# PCB_Oven_Sch.net
KiCad netlist of a schematic drawn in Altium Designer
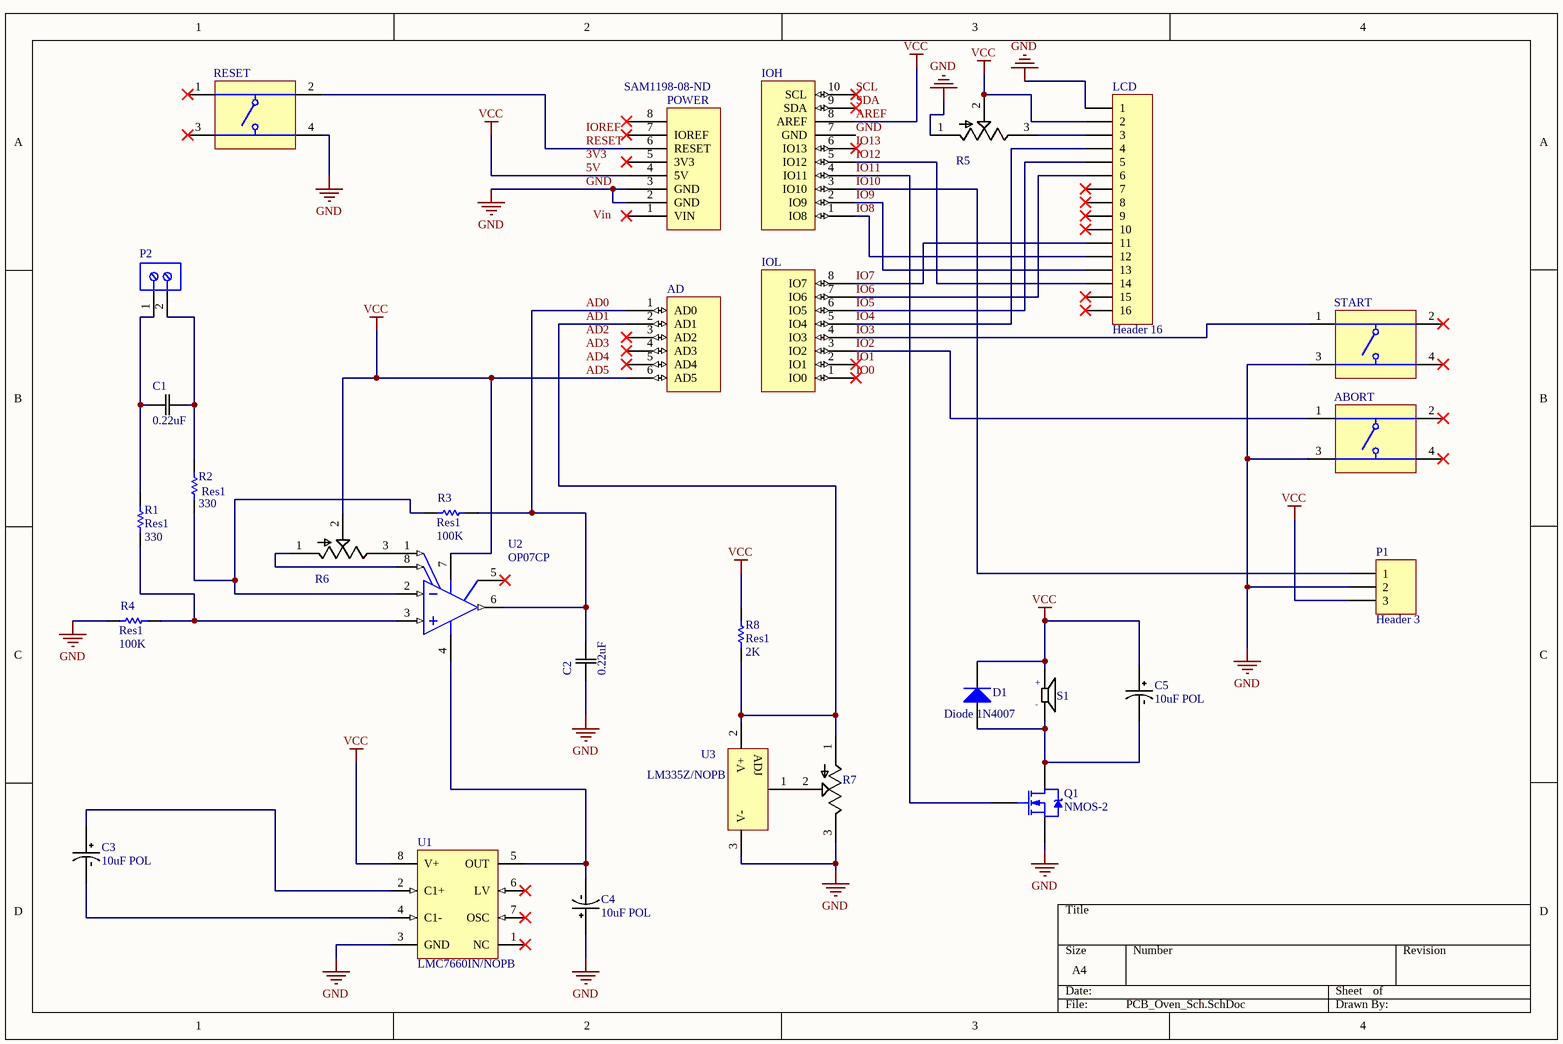
[diagram p0: PCB_Oven_Sch.SchDoc]

(export (version "E")
  (design (tool "Eeschema 10.0.6"))
  (components
    (comp (ref "ABORT")
      (value "1825910-6")
      (footprint "TECO-1825910-6_V")
      (description "Tact Switch, SPST-NO, 0.05 A, -35 to 85 degC, 4-Pin THD, RoHS, Bulk")
      (fields (field (name "MANUFACTURER") "TE Connectivity"))
      (libsource (lib "Altium Content Vault") (part "SW-SPST-4_A"))
    )
    (comp (ref "AD")
      (value "AD")
      (footprint "Header:Header 6x1 8.5mm")
      (libsource (lib "Header") (part "AD"))
    )
    (comp (ref "C1")
      (value "0.22uF")
      (footprint "0.22uF Thru hole")
      (description "CAP CER 0.22UF 200V")
      (fields (field (name "MP") "C317C221K2G5TA7301") (field (name "MF") "KEMET"))
      (libsource (lib "AltiumLibraries") (part "CAP 0.22uF"))
    )
    (comp (ref "C2")
      (value "0.22uF")
      (footprint "0.22uF Thru hole")
      (description "CAP CER 0.22UF 200V")
      (fields (field (name "MP") "C317C221K2G5TA7301") (field (name "MF") "KEMET"))
      (libsource (lib "AltiumLibraries") (part "CAP 0.22uF"))
    )
    (comp (ref "C3")
      (value "10uF POL")
      (footprint "CAP POL 10uF THRU")
      (description "CAP ALUM 10UF 20% 50V RADIAL")
      (fields (field (name "TOLERANCE") "20%") (field (name "MP") "ECA-1HM100I"))
      (libsource (lib "AltiumLibraries") (part "CAP POL 10uF THRU"))
    )
    (comp (ref "C4")
      (value "10uF POL")
      (footprint "CAP POL 10uF THRU")
      (description "CAP ALUM 10UF 20% 50V RADIAL")
      (fields (field (name "TOLERANCE") "20%") (field (name "MP") "ECA-1HM100I"))
      (libsource (lib "AltiumLibraries") (part "CAP POL 10uF THRU"))
    )
    (comp (ref "C5")
      (value "10uF POL")
      (footprint "CAP POL 10uF THRU")
      (description "CAP ALUM 10UF 20% 50V RADIAL")
      (fields (field (name "TOLERANCE") "20%") (field (name "MP") "ECA-1HM100I"))
      (libsource (lib "AltiumLibraries") (part "CAP POL 10uF THRU"))
    )
    (comp (ref "D1")
      (value "Diode 1N4007")
      (footprint "DO-41")
      (description "1 Amp General Purpose Rectifier")
      (fields (field (name "PUBLISHER") "Altium Limited"))
      (libsource (lib "Miscellaneous Devices") (part "Diode 1N4007"))
    )
    (comp (ref "IOH")
      (value "IOH")
      (footprint "Header:Header 10x1 8.5mm")
      (libsource (lib "Header") (part "IOH"))
    )
    (comp (ref "IOL") (value "IOL") (footprint "Header 8x1 8.5mm") (libsource (lib "Header") (part "IOL")))
    (comp (ref "LCD")
      (value "Header 16")
      (footprint "HDR1X16")
      (description "Header, 16-Pin")
      (fields (field (name "PUBLISHER") "Altium Limited"))
      (libsource (lib "Miscellaneous Connectors") (part "Header 16"))
    )
    (comp (ref "P1")
      (value "Header 3")
      (footprint "HDR1X3")
      (description "Header, 3-Pin")
      (fields (field (name "PUBLISHER") "Altium Limited"))
      (libsource (lib "Miscellaneous Connectors") (part "Header 3"))
    )
    (comp (ref "P2")
      (value "282836-2")
      (footprint "TECO-282836-2_V")
      (description "Female Header, Pitch 5 mm, 1 x 2 Position, Height 10 mm, Tail Length 3.5 mm, Rohs, Bulk")
      (fields (field (name "VOLTAGE") "300V") (field (name "MANUFACTURER") "TE Connectivity"))
      (libsource (lib "Altium Content Vault") (part "CN-1P-F-TB2"))
    )
    (comp (ref "POWER")
      (value "POWER_UNO")
      (footprint "Header 8x1 8.5mm")
      (fields (field (name "SUPPLIER PART NUMBER 1") "SAM1198-08-ND"))
      (libsource (lib "Header") (part "POWER_UNO"))
    )
    (comp (ref "Q1")
      (value "NMOS-2")
      (footprint "TO-220AB")
      (description "N-Channel Power MOSFET")
      (fields (field (name "PUBLISHER") "Altium Limited"))
      (libsource (lib "Miscellaneous Devices") (part "NMOS-2"))
    )
    (comp (ref "R1")
      (value "Res1")
      (footprint "AXIAL-0.3")
      (description "Resistor")
      (fields (field (name "ALTIUM_VALUE") "330") (field (name "PUBLISHER") "Altium Limited"))
      (libsource (lib "Miscellaneous Devices") (part "Res1"))
    )
    (comp (ref "R2")
      (value "Res1")
      (footprint "AXIAL-0.3")
      (description "Resistor")
      (fields (field (name "ALTIUM_VALUE") "330") (field (name "PUBLISHER") "Altium Limited"))
      (libsource (lib "Miscellaneous Devices") (part "Res1"))
    )
    (comp (ref "R3")
      (value "Res1")
      (footprint "AXIAL-0.3")
      (description "Resistor")
      (fields (field (name "ALTIUM_VALUE") "100K") (field (name "PUBLISHER") "Altium Limited"))
      (libsource (lib "Miscellaneous Devices") (part "Res1"))
    )
    (comp (ref "R4")
      (value "Res1")
      (footprint "AXIAL-0.3")
      (description "Resistor")
      (fields (field (name "ALTIUM_VALUE") "100K") (field (name "PUBLISHER") "Altium Limited"))
      (libsource (lib "Miscellaneous Devices") (part "Res1"))
    )
    (comp (ref "R5")
      (value "20K")
      (footprint "Potentiometer 20K")
      (description "TRIMMER 20K OHM 0.5W PC PIN TOP - Phillips Screw head")
      (fields (field (name "MF") "Bourns Inc.") (field (name "MP") "3362P-1-203RLF"))
      (libsource (lib "AltiumLibraries") (part "POT 20K THRU"))
    )
    (comp (ref "R6")
      (value "20K")
      (footprint "Potentiometer 20K")
      (description "TRIMMER 20K OHM 0.5W PC PIN TOP - Phillips Screw head")
      (fields (field (name "MF") "Bourns Inc.") (field (name "MP") "3362P-1-203RLF"))
      (libsource (lib "AltiumLibraries") (part "POT 20K THRU"))
    )
    (comp (ref "R7")
      (value "20K")
      (footprint "Potentiometer 20K")
      (description "TRIMMER 20K OHM 0.5W PC PIN TOP - Phillips Screw head")
      (fields (field (name "MF") "Bourns Inc.") (field (name "MP") "3362P-1-203RLF"))
      (libsource (lib "AltiumLibraries") (part "POT 20K THRU"))
    )
    (comp (ref "R8")
      (value "Res1")
      (footprint "AXIAL-0.3")
      (description "Resistor")
      (fields (field (name "ALTIUM_VALUE") "2K") (field (name "PUBLISHER") "Altium Limited"))
      (libsource (lib "Miscellaneous Devices") (part "Res1"))
    )
    (comp (ref "RESET")
      (value "1825910-6")
      (footprint "TECO-1825910-6_V")
      (description "Tact Switch, SPST-NO, 0.05 A, -35 to 85 degC, 4-Pin THD, RoHS, Bulk")
      (fields (field (name "MANUFACTURER") "TE Connectivity"))
      (libsource (lib "Altium Content Vault") (part "SW-SPST-4_A"))
    )
    (comp (ref "S1")
      (value "CEM-1203(42) THRU")
      (footprint "CEM-1203")
      (description "35mA 2.048kHz 85dB @ 3.5V")
      (fields (field (name "MP") "CEM-1203(42)") (field (name "MF") "CUI Devices"))
      (libsource (lib "AltiumLibraries") (part "CEM-1203(42) THRU"))
    )
    (comp (ref "START")
      (value "1825910-6")
      (footprint "TECO-1825910-6_V")
      (description "Tact Switch, SPST-NO, 0.05 A, -35 to 85 degC, 4-Pin THD, RoHS, Bulk")
      (fields (field (name "MANUFACTURER") "TE Connectivity"))
      (libsource (lib "Altium Content Vault") (part "SW-SPST-4_A"))
    )
    (comp (ref "U1")
      (value "LMC7660IN/NOPB")
      (footprint "P0008A")
      (description "Switched Capacitor Voltage Converter, 8-pin MDIP, Pb-Free")
      (fields (field (name "MANUFACTURER") "Texas Instruments"))
      (libsource (lib "Altium Content Vault") (part "PM-CHP-LMC7660IM-8"))
    )
    (comp (ref "U2")
      (value "OP07CP")
      (footprint "P0008A")
      (description "Low-Offset Voltage Operational Amplifier, 6 to 36 V, 0 to 70 degC, 8-pin DIP (P8), Pb-Free (RoHS)")
      (fields (field (name "MANUFACTURER") "Texas Instruments"))
      (libsource (lib "Altium Content Vault") (part "TI-OP07X-X8"))
    )
    (comp (ref "U3")
      (value "LM335Z/NOPB")
      (footprint "LP0003A")
      (description "Precision Temperature Sensor, 3-pin TO-92, Pb-Free")
      (fields (field (name "MANUFACTURER") "Texas Instruments"))
      (libsource (lib "Altium Content Vault") (part "SEN-TEMP-LM335-3"))
    )
  )
  (nets
    (net (code "3") (name "/AD0") (class "Default")
      (node (ref "AD") (pin "1") (pinfunction "AD0_1") (pintype "bidirectional"))
      (node (ref "C2") (pin "2") (pinfunction "C2_2") (pintype "passive"))
      (node (ref "R3") (pin "1") (pinfunction "1_1") (pintype "passive"))
      (node (ref "U2") (pin "6") (pinfunction "OUT_6") (pintype "output"))
    )
    (net (code "4") (name "/AD1") (class "Default")
      (node (ref "AD") (pin "2") (pinfunction "AD1_2") (pintype "bidirectional"))
      (node (ref "R7") (pin "1") (pinfunction "CCW_1") (pintype "passive"))
      (node (ref "R8") (pin "2") (pinfunction "2_2") (pintype "passive"))
      (node (ref "U3") (pin "2") (pinfunction "V+_2") (pintype "passive"))
    )
    (net (code "8") (name "/IO0") (class "Default")
      (node (ref "IOL") (pin "1") (pinfunction "IO0_1") (pintype "bidirectional+no_connect"))
    )
    (net (code "9") (name "/IO1") (class "Default")
      (node (ref "IOL") (pin "2") (pinfunction "IO1_2") (pintype "bidirectional+no_connect"))
    )
    (net (code "10") (name "/IO2") (class "Default")
      (node (ref "ABORT") (pin "1") (pinfunction "1_1") (pintype "passive"))
      (node (ref "IOL") (pin "3") (pinfunction "IO2_3") (pintype "bidirectional"))
    )
    (net (code "11") (name "/IO3") (class "Default")
      (node (ref "IOL") (pin "4") (pinfunction "IO3_4") (pintype "bidirectional"))
      (node (ref "START") (pin "1") (pinfunction "1_1") (pintype "passive"))
    )
    (net (code "12") (name "/IO4") (class "Default")
      (node (ref "IOL") (pin "5") (pinfunction "IO4_5") (pintype "bidirectional"))
      (node (ref "LCD") (pin "4") (pinfunction "4_4") (pintype "passive"))
    )
    (net (code "13") (name "/IO5") (class "Default")
      (node (ref "IOL") (pin "6") (pinfunction "IO5_6") (pintype "bidirectional"))
      (node (ref "LCD") (pin "5") (pinfunction "5_5") (pintype "passive"))
    )
    (net (code "14") (name "/IO6") (class "Default")
      (node (ref "IOL") (pin "7") (pinfunction "IO6_7") (pintype "bidirectional"))
      (node (ref "LCD") (pin "6") (pinfunction "6_6") (pintype "passive"))
    )
    (net (code "15") (name "/IO7") (class "Default")
      (node (ref "IOL") (pin "8") (pinfunction "IO7_8") (pintype "bidirectional"))
      (node (ref "LCD") (pin "11") (pinfunction "11_11") (pintype "passive"))
    )
    (net (code "16") (name "/IO8") (class "Default")
      (node (ref "IOH") (pin "1") (pinfunction "IO8_1") (pintype "bidirectional"))
      (node (ref "LCD") (pin "12") (pinfunction "12_12") (pintype "passive"))
    )
    (net (code "17") (name "/IO9") (class "Default")
      (node (ref "IOH") (pin "2") (pinfunction "IO9_2") (pintype "bidirectional"))
      (node (ref "LCD") (pin "13") (pinfunction "13_13") (pintype "passive"))
    )
    (net (code "18") (name "/IO10") (class "Default")
      (node (ref "IOH") (pin "3") (pinfunction "IO10_3") (pintype "bidirectional"))
      (node (ref "P1") (pin "1") (pinfunction "1_1") (pintype "passive"))
    )
    (net (code "19") (name "/IO11") (class "Default")
      (node (ref "IOH") (pin "4") (pinfunction "IO11_4") (pintype "bidirectional"))
      (node (ref "Q1") (pin "1") (pinfunction "G_1") (pintype "passive"))
    )
    (net (code "20") (name "/IO12") (class "Default")
      (node (ref "IOH") (pin "5") (pinfunction "IO12_5") (pintype "bidirectional"))
      (node (ref "LCD") (pin "14") (pinfunction "14_14") (pintype "passive"))
    )
    (net (code "21") (name "/IO13") (class "Default")
      (node (ref "IOH") (pin "6") (pinfunction "IO13_6") (pintype "bidirectional+no_connect"))
    )
    (net (code "23") (name "/RESET") (class "Default")
      (node (ref "POWER") (pin "6") (pinfunction "RESET_6") (pintype "passive"))
      (node (ref "RESET") (pin "2") (pinfunction "2_2") (pintype "passive"))
    )
    (net (code "24") (name "/SCL") (class "Default")
      (node (ref "IOH") (pin "10") (pinfunction "SCL_10") (pintype "bidirectional+no_connect"))
    )
    (net (code "25") (name "/SDA") (class "Default")
      (node (ref "IOH") (pin "9") (pinfunction "SDA_9") (pintype "bidirectional+no_connect"))
    )
    (net (code "27") (name "GND") (class "Default")
      (node (ref "ABORT") (pin "3") (pinfunction "3_3") (pintype "passive"))
      (node (ref "C2") (pin "1") (pinfunction "C1_1") (pintype "passive"))
      (node (ref "C4") (pin "POS") (pinfunction "POS_POS") (pintype "passive"))
      (node (ref "IOH") (pin "7") (pinfunction "GND_7") (pintype "power_in"))
      (node (ref "LCD") (pin "1") (pinfunction "1_1") (pintype "passive"))
      (node (ref "P1") (pin "2") (pinfunction "2_2") (pintype "passive"))
      (node (ref "POWER") (pin "2") (pinfunction "GND_2") (pintype "power_in"))
      (node (ref "POWER") (pin "3") (pinfunction "GND_3") (pintype "power_in"))
      (node (ref "Q1") (pin "3") (pinfunction "S_3") (pintype "passive"))
      (node (ref "R4") (pin "2") (pinfunction "2_2") (pintype "passive"))
      (node (ref "R5") (pin "1") (pinfunction "CCW_1") (pintype "passive"))
      (node (ref "R7") (pin "3") (pinfunction "CW_3") (pintype "passive"))
      (node (ref "RESET") (pin "4") (pinfunction "4_4") (pintype "passive"))
      (node (ref "START") (pin "3") (pinfunction "3_3") (pintype "passive"))
      (node (ref "U1") (pin "3") (pinfunction "GND_3") (pintype "power_in"))
      (node (ref "U3") (pin "3") (pinfunction "V-_3") (pintype "passive"))
    )
    (net (code "28") (name "Net-(C1-C1)") (class "Default")
      (node (ref "C1") (pin "1") (pinfunction "C1_1") (pintype "passive"))
      (node (ref "P2") (pin "1") (pinfunction "1_1") (pintype "passive"))
      (node (ref "R1") (pin "2") (pinfunction "2_2") (pintype "passive"))
    )
    (net (code "29") (name "Net-(C1-C2)") (class "Default")
      (node (ref "C1") (pin "2") (pinfunction "C2_2") (pintype "passive"))
      (node (ref "P2") (pin "2") (pinfunction "2_2") (pintype "passive"))
      (node (ref "R2") (pin "2") (pinfunction "2_2") (pintype "passive"))
    )
    (net (code "30") (name "Net-(D1-A)") (class "Default")
      (node (ref "C5") (pin "NEG") (pinfunction "NEG_NEG") (pintype "passive"))
      (node (ref "D1") (pin "1") (pinfunction "A_1") (pintype "passive"))
      (node (ref "Q1") (pin "2") (pinfunction "D_2") (pintype "passive"))
      (node (ref "S1") (pin "N") (pinfunction "N_N") (pintype "passive"))
    )
    (net (code "31") (name "Net-(R5-CW)") (class "Default")
      (node (ref "LCD") (pin "3") (pinfunction "3_3") (pintype "passive"))
      (node (ref "R5") (pin "3") (pinfunction "CW_3") (pintype "passive"))
    )
    (net (code "32") (name "Net-(R6-CCW)") (class "Default")
      (node (ref "R6") (pin "1") (pinfunction "CCW_1") (pintype "passive"))
      (node (ref "U2") (pin "8") (pinfunction "OFFSET_N2_8") (pintype "input"))
    )
    (net (code "33") (name "Net-(R6-CW)") (class "Default")
      (node (ref "R6") (pin "3") (pinfunction "CW_3") (pintype "passive"))
      (node (ref "U2") (pin "1") (pinfunction "OFFSET_N1_1") (pintype "input"))
    )
    (net (code "34") (name "Net-(R7-WIPER)") (class "Default")
      (node (ref "R7") (pin "2") (pinfunction "WIPER_2") (pintype "passive"))
      (node (ref "U3") (pin "1") (pinfunction "ADJ_1") (pintype "passive"))
    )
    (net (code "35") (name "Net-(U1-C1+)") (class "Default")
      (node (ref "C3") (pin "POS") (pinfunction "POS_POS") (pintype "passive"))
      (node (ref "U1") (pin "2") (pinfunction "C1+_2") (pintype "input"))
    )
    (net (code "36") (name "Net-(U1-C1-)") (class "Default")
      (node (ref "C3") (pin "NEG") (pinfunction "NEG_NEG") (pintype "passive"))
      (node (ref "U1") (pin "4") (pinfunction "C1-_4") (pintype "input"))
    )
    (net (code "37") (name "Net-(U1-OUT)") (class "Default")
      (node (ref "C4") (pin "NEG") (pinfunction "NEG_NEG") (pintype "passive"))
      (node (ref "U1") (pin "5") (pinfunction "OUT_5") (pintype "power_in"))
      (node (ref "U2") (pin "4") (pinfunction "VCC-_4") (pintype "power_in"))
    )
    (net (code "38") (name "Net-(U2-IN+)") (class "Default")
      (node (ref "R1") (pin "1") (pinfunction "1_1") (pintype "passive"))
      (node (ref "R4") (pin "1") (pinfunction "1_1") (pintype "passive"))
      (node (ref "U2") (pin "3") (pinfunction "IN+_3") (pintype "input"))
    )
    (net (code "39") (name "Net-(U2-IN-)") (class "Default")
      (node (ref "R2") (pin "1") (pinfunction "1_1") (pintype "passive"))
      (node (ref "R3") (pin "2") (pinfunction "2_2") (pintype "passive"))
      (node (ref "U2") (pin "2") (pinfunction "IN-_2") (pintype "input"))
    )
    (net (code "40") (name "VCC") (class "Default")
      (node (ref "AD") (pin "6") (pinfunction "AD5_6") (pintype "bidirectional"))
      (node (ref "C5") (pin "POS") (pinfunction "POS_POS") (pintype "passive"))
      (node (ref "D1") (pin "2") (pinfunction "K_2") (pintype "passive"))
      (node (ref "IOH") (pin "8") (pinfunction "AREF_8") (pintype "passive"))
      (node (ref "LCD") (pin "2") (pinfunction "2_2") (pintype "passive"))
      (node (ref "P1") (pin "3") (pinfunction "3_3") (pintype "passive"))
      (node (ref "POWER") (pin "4") (pinfunction "5V_4") (pintype "power_in"))
      (node (ref "R5") (pin "2") (pinfunction "WIPER_2") (pintype "passive"))
      (node (ref "R6") (pin "2") (pinfunction "WIPER_2") (pintype "passive"))
      (node (ref "R8") (pin "1") (pinfunction "1_1") (pintype "passive"))
      (node (ref "S1") (pin "P") (pinfunction "P_P") (pintype "passive"))
      (node (ref "U1") (pin "8") (pinfunction "V+_8") (pintype "power_in"))
      (node (ref "U2") (pin "7") (pinfunction "VCC+_7") (pintype "power_in"))
    )
    (net (code "41") (name "unconnected-(ABORT-Pad2)") (class "Default")
      (node (ref "ABORT") (pin "2") (pinfunction "2_2") (pintype "passive+no_connect"))
    )
    (net (code "42") (name "unconnected-(ABORT-Pad4)") (class "Default")
      (node (ref "ABORT") (pin "4") (pinfunction "4_4") (pintype "passive+no_connect"))
    )
    (net (code "43") (name "unconnected-(AD-AD2-Pad3)") (class "Default")
      (node (ref "AD") (pin "3") (pinfunction "AD2_3") (pintype "bidirectional+no_connect"))
    )
    (net (code "44") (name "unconnected-(AD-AD3-Pad4)") (class "Default")
      (node (ref "AD") (pin "4") (pinfunction "AD3_4") (pintype "bidirectional+no_connect"))
    )
    (net (code "45") (name "unconnected-(AD-AD4-Pad5)") (class "Default")
      (node (ref "AD") (pin "5") (pinfunction "AD4_5") (pintype "bidirectional+no_connect"))
    )
    (net (code "46") (name "unconnected-(LCD-Pad7)") (class "Default")
      (node (ref "LCD") (pin "7") (pinfunction "7_7") (pintype "passive+no_connect"))
    )
    (net (code "47") (name "unconnected-(LCD-Pad8)") (class "Default")
      (node (ref "LCD") (pin "8") (pinfunction "8_8") (pintype "passive+no_connect"))
    )
    (net (code "48") (name "unconnected-(LCD-Pad9)") (class "Default")
      (node (ref "LCD") (pin "9") (pinfunction "9_9") (pintype "passive+no_connect"))
    )
    (net (code "49") (name "unconnected-(LCD-Pad10)") (class "Default")
      (node (ref "LCD") (pin "10") (pinfunction "10_10") (pintype "passive+no_connect"))
    )
    (net (code "50") (name "unconnected-(LCD-Pad15)") (class "Default")
      (node (ref "LCD") (pin "15") (pinfunction "15_15") (pintype "passive+no_connect"))
    )
    (net (code "51") (name "unconnected-(LCD-Pad16)") (class "Default")
      (node (ref "LCD") (pin "16") (pinfunction "16_16") (pintype "passive+no_connect"))
    )
    (net (code "52") (name "unconnected-(POWER-3V3-Pad5)") (class "Default")
      (node (ref "POWER") (pin "5") (pinfunction "3V3_5") (pintype "power_in+no_connect"))
    )
    (net (code "53") (name "unconnected-(POWER-IOREF-Pad7)") (class "Default")
      (node (ref "POWER") (pin "7") (pinfunction "IOREF_7") (pintype "power_in+no_connect"))
    )
    (net (code "54") (name "unconnected-(POWER-Pad8)") (class "Default")
      (node (ref "POWER") (pin "8") (pintype "passive+no_connect"))
    )
    (net (code "55") (name "unconnected-(POWER-VIN-Pad1)") (class "Default")
      (node (ref "POWER") (pin "1") (pinfunction "VIN_1") (pintype "power_in+no_connect"))
    )
    (net (code "56") (name "unconnected-(RESET-Pad1)") (class "Default")
      (node (ref "RESET") (pin "1") (pinfunction "1_1") (pintype "passive+no_connect"))
    )
    (net (code "57") (name "unconnected-(RESET-Pad3)") (class "Default")
      (node (ref "RESET") (pin "3") (pinfunction "3_3") (pintype "passive+no_connect"))
    )
    (net (code "58") (name "unconnected-(START-Pad2)") (class "Default")
      (node (ref "START") (pin "2") (pinfunction "2_2") (pintype "passive+no_connect"))
    )
    (net (code "59") (name "unconnected-(START-Pad4)") (class "Default")
      (node (ref "START") (pin "4") (pinfunction "4_4") (pintype "passive+no_connect"))
    )
    (net (code "60") (name "unconnected-(U1-LV-Pad6)") (class "Default")
      (node (ref "U1") (pin "6") (pinfunction "LV_6") (pintype "input+no_connect"))
    )
    (net (code "61") (name "unconnected-(U1-NC-Pad1)") (class "Default")
      (node (ref "U1") (pin "1") (pinfunction "NC_1") (pintype "passive+no_connect"))
    )
    (net (code "62") (name "unconnected-(U1-OSC-Pad7)") (class "Default")
      (node (ref "U1") (pin "7") (pinfunction "OSC_7") (pintype "input+no_connect"))
    )
    (net (code "63") (name "unconnected-(U2-NC-Pad5)") (class "Default")
      (node (ref "U2") (pin "5") (pinfunction "NC_5") (pintype "passive+no_connect"))
    )
  )
)
